# CPU.net
KiCad netlist of a schematic drawn in Altium Designer
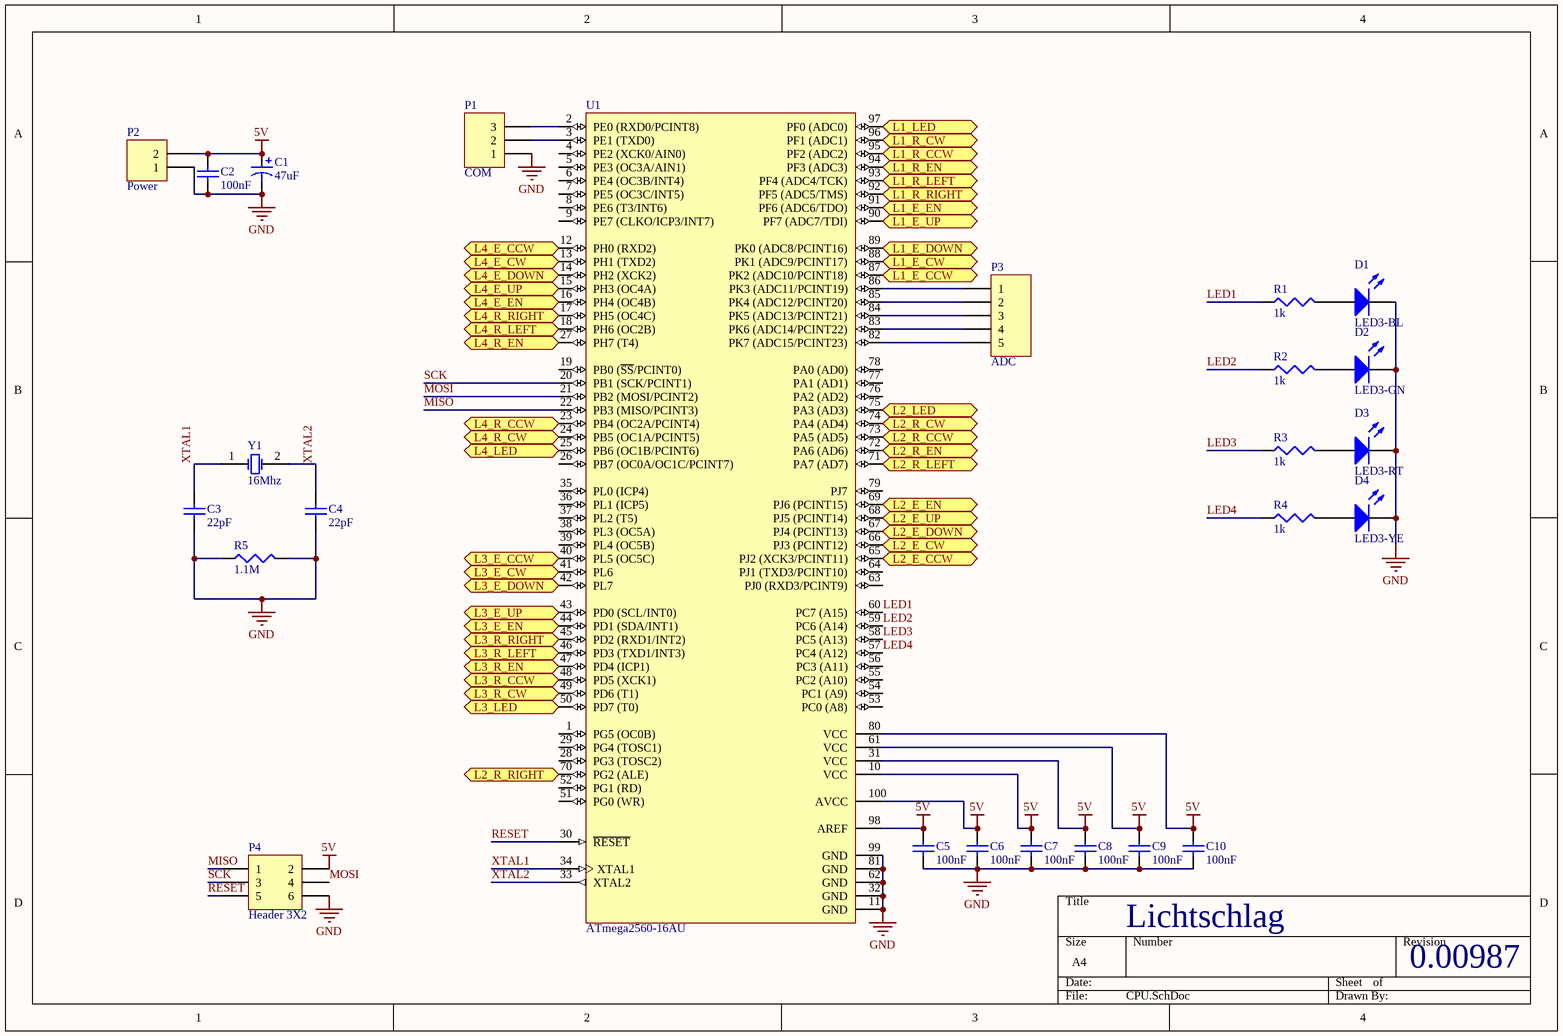
[diagram p0: CPU.SchDoc]

(export (version "E")
  (design (tool "Eeschema 10.0.6"))
  (components
    (comp (ref "C1")
      (value "47uF")
      (footprint "2220")
      (description "Polarized Capacitor (Surface Mount)")
      (fields (field (name "PUBLISHER") "Altium Limited"))
      (libsource (lib "Miscellaneous Devices") (part "Cap Pol3"))
    )
    (comp (ref "C2")
      (value "100nF")
      (footprint "2220")
      (description "Capacitor (Semiconductor SIM Model)")
      (fields (field (name "PUBLISHER") "Altium Limited"))
      (libsource (lib "Miscellaneous Devices") (part "Cap Semi"))
    )
    (comp (ref "C3")
      (value "22pF")
      (footprint "Miscellaneous Devices:6-0805_N")
      (description "Capacitor (Semiconductor SIM Model)")
      (fields (field (name "PUBLISHER") "Altium Limited"))
      (libsource (lib "Miscellaneous Devices") (part "Cap Semi"))
    )
    (comp (ref "C4")
      (value "22pF")
      (footprint "6-0805_N")
      (description "Capacitor (Semiconductor SIM Model)")
      (fields (field (name "PUBLISHER") "Altium Limited"))
      (libsource (lib "Miscellaneous Devices") (part "Cap Semi"))
    )
    (comp (ref "C5")
      (value "100nF")
      (footprint "2220")
      (description "Capacitor (Semiconductor SIM Model)")
      (fields (field (name "PUBLISHER") "Altium Limited"))
      (libsource (lib "Miscellaneous Devices") (part "Cap Semi"))
    )
    (comp (ref "C6")
      (value "100nF")
      (footprint "2220")
      (description "Capacitor (Semiconductor SIM Model)")
      (fields (field (name "PUBLISHER") "Altium Limited"))
      (libsource (lib "Miscellaneous Devices") (part "Cap Semi"))
    )
    (comp (ref "C7")
      (value "100nF")
      (footprint "2220")
      (description "Capacitor (Semiconductor SIM Model)")
      (fields (field (name "PUBLISHER") "Altium Limited"))
      (libsource (lib "Miscellaneous Devices") (part "Cap Semi"))
    )
    (comp (ref "C8")
      (value "100nF")
      (footprint "2220")
      (description "Capacitor (Semiconductor SIM Model)")
      (fields (field (name "PUBLISHER") "Altium Limited"))
      (libsource (lib "Miscellaneous Devices") (part "Cap Semi"))
    )
    (comp (ref "C9")
      (value "100nF")
      (footprint "2220")
      (description "Capacitor (Semiconductor SIM Model)")
      (fields (field (name "PUBLISHER") "Altium Limited"))
      (libsource (lib "Miscellaneous Devices") (part "Cap Semi"))
    )
    (comp (ref "C10")
      (value "100nF")
      (footprint "2220")
      (description "Capacitor (Semiconductor SIM Model)")
      (fields (field (name "PUBLISHER") "Altium Limited"))
      (libsource (lib "Miscellaneous Devices") (part "Cap Semi"))
    )
    (comp (ref "D1")
      (value "LED3-BL")
      (footprint "6-0805_N")
      (description "Typical BLUE SiC LED")
      (fields (field (name "PUBLISHER") "Altium Limited"))
      (libsource (lib "Miscellaneous Devices") (part "LED3"))
    )
    (comp (ref "D2")
      (value "LED3-GN")
      (footprint "6-0805_N")
      (description "Typical BLUE SiC LED")
      (fields (field (name "PUBLISHER") "Altium Limited"))
      (libsource (lib "Miscellaneous Devices") (part "LED3"))
    )
    (comp (ref "D3")
      (value "LED3-RT")
      (footprint "6-0805_N")
      (description "Typical BLUE SiC LED")
      (fields (field (name "PUBLISHER") "Altium Limited"))
      (libsource (lib "Miscellaneous Devices") (part "LED3"))
    )
    (comp (ref "D4")
      (value "LED3-YE")
      (footprint "6-0805_N")
      (description "Typical BLUE SiC LED")
      (fields (field (name "PUBLISHER") "Altium Limited"))
      (libsource (lib "Miscellaneous Devices") (part "LED3"))
    )
    (comp (ref "P1")
      (value "COM")
      (footprint "HDR1X3")
      (description "Header, 3-Pin")
      (fields (field (name "PUBLISHER") "Altium Limited"))
      (libsource (lib "Miscellaneous Connectors") (part "Header 3"))
    )
    (comp (ref "P2")
      (value "Power")
      (footprint "HDR1X2")
      (description "Header, 2-Pin")
      (fields (field (name "PUBLISHER") "Altium Limited"))
      (libsource (lib "Miscellaneous Connectors") (part "Header 2"))
    )
    (comp (ref "P3")
      (value "ADC")
      (footprint "HDR1X5")
      (description "Header, 5-Pin")
      (fields (field (name "PUBLISHER") "Altium Limited"))
      (libsource (lib "Miscellaneous Connectors") (part "Header 5"))
    )
    (comp (ref "P4")
      (value "Header 3X2")
      (footprint "HDR2X3")
      (description "Header, 3-Pin, Dual row")
      (fields (field (name "PUBLISHER") "Altium Limited"))
      (libsource (lib "Miscellaneous Connectors") (part "Header 3X2"))
    )
    (comp (ref "R1")
      (value "1k")
      (footprint "6-0805_N")
      (description "Resistor")
      (fields (field (name "PUBLISHER") "Altium Limited"))
      (libsource (lib "Miscellaneous Devices") (part "Res3"))
    )
    (comp (ref "R2")
      (value "1k")
      (footprint "6-0805_N")
      (description "Resistor")
      (fields (field (name "PUBLISHER") "Altium Limited"))
      (libsource (lib "Miscellaneous Devices") (part "Res3"))
    )
    (comp (ref "R3")
      (value "1k")
      (footprint "6-0805_N")
      (description "Resistor")
      (fields (field (name "PUBLISHER") "Altium Limited"))
      (libsource (lib "Miscellaneous Devices") (part "Res3"))
    )
    (comp (ref "R4")
      (value "1k")
      (footprint "6-0805_N")
      (description "Resistor")
      (fields (field (name "PUBLISHER") "Altium Limited"))
      (libsource (lib "Miscellaneous Devices") (part "Res3"))
    )
    (comp (ref "R5")
      (value "1.1M")
      (footprint "6-0805_N")
      (description "Resistor")
      (fields (field (name "PUBLISHER") "Altium Limited"))
      (libsource (lib "Miscellaneous Devices") (part "Res3"))
    )
    (comp (ref "U1")
      (value "ATmega2560-16AU")
      (footprint "100A_M")
      (libsource (lib "Altium Content Vault") (part "CMP-0095-00210-2"))
    )
    (comp (ref "Y1")
      (value "16Mhz")
      (footprint "R38")
      (description "Crystal Oscillator")
      (fields (field (name "PUBLISHER") "Altium Limited"))
      (libsource (lib "Miscellaneous Devices") (part "XTAL"))
    )
  )
  (nets
    (net (code "1") (name "/L1_E_CCW") (class "Default")
      (node (ref "U1") (pin "87") (pinfunction "PK2_(ADC10/PCINT18)_87") (pintype "bidirectional"))
    )
    (net (code "2") (name "/L1_E_CW") (class "Default")
      (node (ref "U1") (pin "88") (pinfunction "PK1_(ADC9/PCINT17)_88") (pintype "bidirectional"))
    )
    (net (code "3") (name "/L1_E_DOWN") (class "Default")
      (node (ref "U1") (pin "89") (pinfunction "PK0_(ADC8/PCINT16)_89") (pintype "bidirectional"))
    )
    (net (code "4") (name "/L1_E_EN") (class "Default")
      (node (ref "U1") (pin "91") (pinfunction "PF6_(ADC6/TDO)_91") (pintype "bidirectional"))
    )
    (net (code "5") (name "/L1_E_UP") (class "Default")
      (node (ref "U1") (pin "90") (pinfunction "PF7_(ADC7/TDI)_90") (pintype "bidirectional"))
    )
    (net (code "6") (name "/L1_LED") (class "Default")
      (node (ref "U1") (pin "97") (pinfunction "PF0_(ADC0)_97") (pintype "bidirectional"))
    )
    (net (code "7") (name "/L1_R_CCW") (class "Default")
      (node (ref "U1") (pin "95") (pinfunction "PF2_(ADC2)_95") (pintype "bidirectional"))
    )
    (net (code "8") (name "/L1_R_CW") (class "Default")
      (node (ref "U1") (pin "96") (pinfunction "PF1_(ADC1)_96") (pintype "bidirectional"))
    )
    (net (code "9") (name "/L1_R_EN") (class "Default")
      (node (ref "U1") (pin "94") (pinfunction "PF3_(ADC3)_94") (pintype "bidirectional"))
    )
    (net (code "10") (name "/L1_R_LEFT") (class "Default")
      (node (ref "U1") (pin "93") (pinfunction "PF4_(ADC4/TCK)_93") (pintype "bidirectional"))
    )
    (net (code "11") (name "/L1_R_RIGHT") (class "Default")
      (node (ref "U1") (pin "92") (pinfunction "PF5_(ADC5/TMS)_92") (pintype "bidirectional"))
    )
    (net (code "12") (name "/L2_E_CCW") (class "Default")
      (node (ref "U1") (pin "65") (pinfunction "PJ2_(XCK3/PCINT11)_65") (pintype "bidirectional"))
    )
    (net (code "13") (name "/L2_E_CW") (class "Default")
      (node (ref "U1") (pin "66") (pinfunction "PJ3_(PCINT12)_66") (pintype "bidirectional"))
    )
    (net (code "14") (name "/L2_E_DOWN") (class "Default")
      (node (ref "U1") (pin "67") (pinfunction "PJ4_(PCINT13)_67") (pintype "bidirectional"))
    )
    (net (code "15") (name "/L2_E_EN") (class "Default")
      (node (ref "U1") (pin "69") (pinfunction "PJ6_(PCINT15)_69") (pintype "bidirectional"))
    )
    (net (code "16") (name "/L2_E_UP") (class "Default")
      (node (ref "U1") (pin "68") (pinfunction "PJ5_(PCINT14)_68") (pintype "bidirectional"))
    )
    (net (code "17") (name "/L2_LED") (class "Default")
      (node (ref "U1") (pin "75") (pinfunction "PA3_(AD3)_75") (pintype "bidirectional"))
    )
    (net (code "18") (name "/L2_R_CCW") (class "Default")
      (node (ref "U1") (pin "73") (pinfunction "PA5_(AD5)_73") (pintype "bidirectional"))
    )
    (net (code "19") (name "/L2_R_CW") (class "Default")
      (node (ref "U1") (pin "74") (pinfunction "PA4_(AD4)_74") (pintype "bidirectional"))
    )
    (net (code "20") (name "/L2_R_EN") (class "Default")
      (node (ref "U1") (pin "72") (pinfunction "PA6_(AD6)_72") (pintype "bidirectional"))
    )
    (net (code "21") (name "/L2_R_LEFT") (class "Default")
      (node (ref "U1") (pin "71") (pinfunction "PA7_(AD7)_71") (pintype "bidirectional"))
    )
    (net (code "22") (name "/L2_R_RIGHT") (class "Default")
      (node (ref "U1") (pin "70") (pinfunction "PG2_(ALE)_70") (pintype "bidirectional"))
    )
    (net (code "23") (name "/L3_E_CCW") (class "Default")
      (node (ref "U1") (pin "40") (pinfunction "PL5_(OC5C)_40") (pintype "bidirectional"))
    )
    (net (code "24") (name "/L3_E_CW") (class "Default")
      (node (ref "U1") (pin "41") (pinfunction "PL6_41") (pintype "bidirectional"))
    )
    (net (code "25") (name "/L3_E_DOWN") (class "Default")
      (node (ref "U1") (pin "42") (pinfunction "PL7_42") (pintype "bidirectional"))
    )
    (net (code "26") (name "/L3_E_EN") (class "Default")
      (node (ref "U1") (pin "44") (pinfunction "PD1_(SDA/INT1)_44") (pintype "bidirectional"))
    )
    (net (code "27") (name "/L3_E_UP") (class "Default")
      (node (ref "U1") (pin "43") (pinfunction "PD0_(SCL/INT0)_43") (pintype "bidirectional"))
    )
    (net (code "28") (name "/L3_LED") (class "Default")
      (node (ref "U1") (pin "50") (pinfunction "PD7_(T0)_50") (pintype "bidirectional"))
    )
    (net (code "29") (name "/L3_R_CCW") (class "Default")
      (node (ref "U1") (pin "48") (pinfunction "PD5_(XCK1)_48") (pintype "bidirectional"))
    )
    (net (code "30") (name "/L3_R_CW") (class "Default")
      (node (ref "U1") (pin "49") (pinfunction "PD6_(T1)_49") (pintype "bidirectional"))
    )
    (net (code "31") (name "/L3_R_EN") (class "Default")
      (node (ref "U1") (pin "47") (pinfunction "PD4_(ICP1)_47") (pintype "bidirectional"))
    )
    (net (code "32") (name "/L3_R_LEFT") (class "Default")
      (node (ref "U1") (pin "46") (pinfunction "PD3_(TXD1/INT3)_46") (pintype "bidirectional"))
    )
    (net (code "33") (name "/L3_R_RIGHT") (class "Default")
      (node (ref "U1") (pin "45") (pinfunction "PD2_(RXD1/INT2)_45") (pintype "bidirectional"))
    )
    (net (code "34") (name "/L4_E_CCW") (class "Default")
      (node (ref "U1") (pin "12") (pinfunction "PH0_(RXD2)_12") (pintype "bidirectional"))
    )
    (net (code "35") (name "/L4_E_CW") (class "Default")
      (node (ref "U1") (pin "13") (pinfunction "PH1_(TXD2)_13") (pintype "bidirectional"))
    )
    (net (code "36") (name "/L4_E_DOWN") (class "Default")
      (node (ref "U1") (pin "14") (pinfunction "PH2_(XCK2)_14") (pintype "bidirectional"))
    )
    (net (code "37") (name "/L4_E_EN") (class "Default")
      (node (ref "U1") (pin "16") (pinfunction "PH4_(OC4B)_16") (pintype "bidirectional"))
    )
    (net (code "38") (name "/L4_E_UP") (class "Default")
      (node (ref "U1") (pin "15") (pinfunction "PH3_(OC4A)_15") (pintype "bidirectional"))
    )
    (net (code "39") (name "/L4_LED") (class "Default")
      (node (ref "U1") (pin "25") (pinfunction "PB6_(OC1B/PCINT6)_25") (pintype "bidirectional"))
    )
    (net (code "40") (name "/L4_R_CCW") (class "Default")
      (node (ref "U1") (pin "23") (pinfunction "PB4_(OC2A/PCINT4)_23") (pintype "bidirectional"))
    )
    (net (code "41") (name "/L4_R_CW") (class "Default")
      (node (ref "U1") (pin "24") (pinfunction "PB5_(OC1A/PCINT5)_24") (pintype "bidirectional"))
    )
    (net (code "42") (name "/L4_R_EN") (class "Default")
      (node (ref "U1") (pin "27") (pinfunction "PH7_(T4)_27") (pintype "bidirectional"))
    )
    (net (code "43") (name "/L4_R_LEFT") (class "Default")
      (node (ref "U1") (pin "18") (pinfunction "PH6_(OC2B)_18") (pintype "bidirectional"))
    )
    (net (code "44") (name "/L4_R_RIGHT") (class "Default")
      (node (ref "U1") (pin "17") (pinfunction "PH5_(OC4C)_17") (pintype "bidirectional"))
    )
    (net (code "45") (name "/LED1") (class "Default")
      (node (ref "R1") (pin "1") (pinfunction "1_1") (pintype "passive"))
      (node (ref "U1") (pin "60") (pinfunction "PC7_(A15)_60") (pintype "bidirectional"))
    )
    (net (code "46") (name "/LED2") (class "Default")
      (node (ref "R2") (pin "1") (pinfunction "1_1") (pintype "passive"))
      (node (ref "U1") (pin "59") (pinfunction "PC6_(A14)_59") (pintype "bidirectional"))
    )
    (net (code "47") (name "/LED3") (class "Default")
      (node (ref "R3") (pin "1") (pinfunction "1_1") (pintype "passive"))
      (node (ref "U1") (pin "58") (pinfunction "PC5_(A13)_58") (pintype "bidirectional"))
    )
    (net (code "48") (name "/LED4") (class "Default")
      (node (ref "R4") (pin "1") (pinfunction "1_1") (pintype "passive"))
      (node (ref "U1") (pin "57") (pinfunction "PC4_(A12)_57") (pintype "bidirectional"))
    )
    (net (code "49") (name "/MISO") (class "Default")
      (node (ref "P4") (pin "1") (pinfunction "1_1") (pintype "passive"))
      (node (ref "U1") (pin "22") (pinfunction "PB3_(MISO/PCINT3)_22") (pintype "bidirectional"))
    )
    (net (code "50") (name "/MOSI") (class "Default")
      (node (ref "P4") (pin "4") (pinfunction "4_4") (pintype "passive"))
      (node (ref "U1") (pin "21") (pinfunction "PB2_(MOSI/PCINT2)_21") (pintype "bidirectional"))
    )
    (net (code "51") (name "/RESET") (class "Default")
      (node (ref "P4") (pin "5") (pinfunction "5_5") (pintype "passive"))
      (node (ref "U1") (pin "30") (pinfunction "~{RESET}_30") (pintype "input"))
    )
    (net (code "52") (name "/SCK") (class "Default")
      (node (ref "P4") (pin "3") (pinfunction "3_3") (pintype "passive"))
      (node (ref "U1") (pin "20") (pinfunction "PB1_(SCK/PCINT1)_20") (pintype "bidirectional"))
    )
    (net (code "53") (name "/XTAL1") (class "Default")
      (node (ref "C3") (pin "2") (pinfunction "2_2") (pintype "passive"))
      (node (ref "U1") (pin "34") (pinfunction "XTAL1_34") (pintype "input"))
      (node (ref "Y1") (pin "1") (pinfunction "OSC1_1") (pintype "passive"))
    )
    (net (code "54") (name "/XTAL2") (class "Default")
      (node (ref "C4") (pin "2") (pinfunction "2_2") (pintype "passive"))
      (node (ref "U1") (pin "33") (pinfunction "XTAL2_33") (pintype "output"))
      (node (ref "Y1") (pin "2") (pinfunction "OSC2_2") (pintype "passive"))
    )
    (net (code "55") (name "5V") (class "Default")
      (node (ref "C1") (pin "1") (pinfunction "1_1") (pintype "passive"))
      (node (ref "C10") (pin "2") (pinfunction "2_2") (pintype "passive"))
      (node (ref "C2") (pin "2") (pinfunction "2_2") (pintype "passive"))
      (node (ref "C5") (pin "2") (pinfunction "2_2") (pintype "passive"))
      (node (ref "C6") (pin "2") (pinfunction "2_2") (pintype "passive"))
      (node (ref "C7") (pin "2") (pinfunction "2_2") (pintype "passive"))
      (node (ref "C8") (pin "2") (pinfunction "2_2") (pintype "passive"))
      (node (ref "C9") (pin "2") (pinfunction "2_2") (pintype "passive"))
      (node (ref "P2") (pin "2") (pinfunction "2_2") (pintype "passive"))
      (node (ref "P4") (pin "2") (pinfunction "2_2") (pintype "passive"))
      (node (ref "U1") (pin "10") (pinfunction "VCC_10") (pintype "power_in"))
      (node (ref "U1") (pin "100") (pinfunction "AVCC_100") (pintype "power_in"))
      (node (ref "U1") (pin "31") (pinfunction "VCC_31") (pintype "power_in"))
      (node (ref "U1") (pin "61") (pinfunction "VCC_61") (pintype "power_in"))
      (node (ref "U1") (pin "80") (pinfunction "VCC_80") (pintype "power_in"))
      (node (ref "U1") (pin "98") (pinfunction "AREF_98") (pintype "power_in"))
    )
    (net (code "56") (name "GND") (class "Default")
      (node (ref "C1") (pin "2") (pinfunction "2_2") (pintype "passive"))
      (node (ref "C10") (pin "1") (pinfunction "1_1") (pintype "passive"))
      (node (ref "C2") (pin "1") (pinfunction "1_1") (pintype "passive"))
      (node (ref "C3") (pin "1") (pinfunction "1_1") (pintype "passive"))
      (node (ref "C4") (pin "1") (pinfunction "1_1") (pintype "passive"))
      (node (ref "C5") (pin "1") (pinfunction "1_1") (pintype "passive"))
      (node (ref "C6") (pin "1") (pinfunction "1_1") (pintype "passive"))
      (node (ref "C7") (pin "1") (pinfunction "1_1") (pintype "passive"))
      (node (ref "C8") (pin "1") (pinfunction "1_1") (pintype "passive"))
      (node (ref "C9") (pin "1") (pinfunction "1_1") (pintype "passive"))
      (node (ref "D1") (pin "2") (pinfunction "K_2") (pintype "passive"))
      (node (ref "D2") (pin "2") (pinfunction "K_2") (pintype "passive"))
      (node (ref "D3") (pin "2") (pinfunction "K_2") (pintype "passive"))
      (node (ref "D4") (pin "2") (pinfunction "K_2") (pintype "passive"))
      (node (ref "P1") (pin "1") (pinfunction "1_1") (pintype "passive"))
      (node (ref "P2") (pin "1") (pinfunction "1_1") (pintype "passive"))
      (node (ref "P4") (pin "6") (pinfunction "6_6") (pintype "passive"))
      (node (ref "R5") (pin "1") (pinfunction "1_1") (pintype "passive"))
      (node (ref "R5") (pin "2") (pinfunction "2_2") (pintype "passive"))
      (node (ref "U1") (pin "11") (pinfunction "GND_11") (pintype "power_in"))
      (node (ref "U1") (pin "32") (pinfunction "GND_32") (pintype "power_in"))
      (node (ref "U1") (pin "62") (pinfunction "GND_62") (pintype "power_in"))
      (node (ref "U1") (pin "81") (pinfunction "GND_81") (pintype "power_in"))
      (node (ref "U1") (pin "99") (pinfunction "GND_99") (pintype "power_in"))
    )
    (net (code "57") (name "Net-(D1-A)") (class "Default")
      (node (ref "D1") (pin "1") (pinfunction "A_1") (pintype "passive"))
      (node (ref "R1") (pin "2") (pinfunction "2_2") (pintype "passive"))
    )
    (net (code "58") (name "Net-(D2-A)") (class "Default")
      (node (ref "D2") (pin "1") (pinfunction "A_1") (pintype "passive"))
      (node (ref "R2") (pin "2") (pinfunction "2_2") (pintype "passive"))
    )
    (net (code "59") (name "Net-(D3-A)") (class "Default")
      (node (ref "D3") (pin "1") (pinfunction "A_1") (pintype "passive"))
      (node (ref "R3") (pin "2") (pinfunction "2_2") (pintype "passive"))
    )
    (net (code "60") (name "Net-(D4-A)") (class "Default")
      (node (ref "D4") (pin "1") (pinfunction "A_1") (pintype "passive"))
      (node (ref "R4") (pin "2") (pinfunction "2_2") (pintype "passive"))
    )
    (net (code "61") (name "Net-(U1-PE0_(RXD0{slash}PCINT8))") (class "Default")
      (node (ref "P1") (pin "3") (pinfunction "3_3") (pintype "passive"))
      (node (ref "U1") (pin "2") (pinfunction "PE0_(RXD0/PCINT8)_2") (pintype "bidirectional"))
    )
    (net (code "62") (name "Net-(U1-PE1_(TXD0))") (class "Default")
      (node (ref "P1") (pin "2") (pinfunction "2_2") (pintype "passive"))
      (node (ref "U1") (pin "3") (pinfunction "PE1_(TXD0)_3") (pintype "bidirectional"))
    )
    (net (code "63") (name "Net-(U1-PK3_(ADC11{slash}PCINT19))") (class "Default")
      (node (ref "P3") (pin "1") (pinfunction "1_1") (pintype "passive"))
      (node (ref "U1") (pin "86") (pinfunction "PK3_(ADC11/PCINT19)_86") (pintype "bidirectional"))
    )
    (net (code "64") (name "Net-(U1-PK4_(ADC12{slash}PCINT20))") (class "Default")
      (node (ref "P3") (pin "2") (pinfunction "2_2") (pintype "passive"))
      (node (ref "U1") (pin "85") (pinfunction "PK4_(ADC12/PCINT20)_85") (pintype "bidirectional"))
    )
    (net (code "65") (name "Net-(U1-PK5_(ADC13{slash}PCINT21))") (class "Default")
      (node (ref "P3") (pin "3") (pinfunction "3_3") (pintype "passive"))
      (node (ref "U1") (pin "84") (pinfunction "PK5_(ADC13/PCINT21)_84") (pintype "bidirectional"))
    )
    (net (code "66") (name "Net-(U1-PK6_(ADC14{slash}PCINT22))") (class "Default")
      (node (ref "P3") (pin "4") (pinfunction "4_4") (pintype "passive"))
      (node (ref "U1") (pin "83") (pinfunction "PK6_(ADC14/PCINT22)_83") (pintype "bidirectional"))
    )
    (net (code "67") (name "Net-(U1-PK7_(ADC15{slash}PCINT23))") (class "Default")
      (node (ref "P3") (pin "5") (pinfunction "5_5") (pintype "passive"))
      (node (ref "U1") (pin "82") (pinfunction "PK7_(ADC15/PCINT23)_82") (pintype "bidirectional"))
    )
    (net (code "68") (name "unconnected-(U1-PA0_(AD0)-Pad78)") (class "Default")
      (node (ref "U1") (pin "78") (pinfunction "PA0_(AD0)_78") (pintype "bidirectional"))
    )
    (net (code "69") (name "unconnected-(U1-PA1_(AD1)-Pad77)") (class "Default")
      (node (ref "U1") (pin "77") (pinfunction "PA1_(AD1)_77") (pintype "bidirectional"))
    )
    (net (code "70") (name "unconnected-(U1-PA2_(AD2)-Pad76)") (class "Default")
      (node (ref "U1") (pin "76") (pinfunction "PA2_(AD2)_76") (pintype "bidirectional"))
    )
    (net (code "71") (name "unconnected-(U1-PB0_(~{SS}{slash}PCINT0)-Pad19)") (class "Default")
      (node (ref "U1") (pin "19") (pinfunction "PB0_(~{SS}/PCINT0)_19") (pintype "bidirectional"))
    )
    (net (code "72") (name "unconnected-(U1-PB7_(OC0A{slash}OC1C{slash}PCINT7)-Pad26)") (class "Default")
      (node (ref "U1") (pin "26") (pinfunction "PB7_(OC0A/OC1C/PCINT7)_26") (pintype "bidirectional"))
    )
    (net (code "73") (name "unconnected-(U1-PC0_(A8)-Pad53)") (class "Default")
      (node (ref "U1") (pin "53") (pinfunction "PC0_(A8)_53") (pintype "bidirectional"))
    )
    (net (code "74") (name "unconnected-(U1-PC1_(A9)-Pad54)") (class "Default")
      (node (ref "U1") (pin "54") (pinfunction "PC1_(A9)_54") (pintype "bidirectional"))
    )
    (net (code "75") (name "unconnected-(U1-PC2_(A10)-Pad55)") (class "Default")
      (node (ref "U1") (pin "55") (pinfunction "PC2_(A10)_55") (pintype "bidirectional"))
    )
    (net (code "76") (name "unconnected-(U1-PC3_(A11)-Pad56)") (class "Default")
      (node (ref "U1") (pin "56") (pinfunction "PC3_(A11)_56") (pintype "bidirectional"))
    )
    (net (code "77") (name "unconnected-(U1-PE2_(XCK0{slash}AIN0)-Pad4)") (class "Default")
      (node (ref "U1") (pin "4") (pinfunction "PE2_(XCK0/AIN0)_4") (pintype "bidirectional"))
    )
    (net (code "78") (name "unconnected-(U1-PE3_(OC3A{slash}AIN1)-Pad5)") (class "Default")
      (node (ref "U1") (pin "5") (pinfunction "PE3_(OC3A/AIN1)_5") (pintype "bidirectional"))
    )
    (net (code "79") (name "unconnected-(U1-PE4_(OC3B{slash}INT4)-Pad6)") (class "Default")
      (node (ref "U1") (pin "6") (pinfunction "PE4_(OC3B/INT4)_6") (pintype "bidirectional"))
    )
    (net (code "80") (name "unconnected-(U1-PE5_(OC3C{slash}INT5)-Pad7)") (class "Default")
      (node (ref "U1") (pin "7") (pinfunction "PE5_(OC3C/INT5)_7") (pintype "bidirectional"))
    )
    (net (code "81") (name "unconnected-(U1-PE6_(T3{slash}INT6)-Pad8)") (class "Default")
      (node (ref "U1") (pin "8") (pinfunction "PE6_(T3/INT6)_8") (pintype "bidirectional"))
    )
    (net (code "82") (name "unconnected-(U1-PE7_(CLKO{slash}ICP3{slash}INT7)-Pad9)") (class "Default")
      (node (ref "U1") (pin "9") (pinfunction "PE7_(CLKO/ICP3/INT7)_9") (pintype "bidirectional"))
    )
    (net (code "83") (name "unconnected-(U1-PG0_(WR)-Pad51)") (class "Default")
      (node (ref "U1") (pin "51") (pinfunction "PG0_(WR)_51") (pintype "bidirectional"))
    )
    (net (code "84") (name "unconnected-(U1-PG1_(RD)-Pad52)") (class "Default")
      (node (ref "U1") (pin "52") (pinfunction "PG1_(RD)_52") (pintype "bidirectional"))
    )
    (net (code "85") (name "unconnected-(U1-PG3_(TOSC2)-Pad28)") (class "Default")
      (node (ref "U1") (pin "28") (pinfunction "PG3_(TOSC2)_28") (pintype "bidirectional"))
    )
    (net (code "86") (name "unconnected-(U1-PG4_(TOSC1)-Pad29)") (class "Default")
      (node (ref "U1") (pin "29") (pinfunction "PG4_(TOSC1)_29") (pintype "bidirectional"))
    )
    (net (code "87") (name "unconnected-(U1-PG5_(OC0B)-Pad1)") (class "Default")
      (node (ref "U1") (pin "1") (pinfunction "PG5_(OC0B)_1") (pintype "bidirectional"))
    )
    (net (code "88") (name "unconnected-(U1-PJ0_(RXD3{slash}PCINT9)-Pad63)") (class "Default")
      (node (ref "U1") (pin "63") (pinfunction "PJ0_(RXD3/PCINT9)_63") (pintype "bidirectional"))
    )
    (net (code "89") (name "unconnected-(U1-PJ1_(TXD3{slash}PCINT10)-Pad64)") (class "Default")
      (node (ref "U1") (pin "64") (pinfunction "PJ1_(TXD3/PCINT10)_64") (pintype "bidirectional"))
    )
    (net (code "90") (name "unconnected-(U1-PJ7-Pad79)") (class "Default")
      (node (ref "U1") (pin "79") (pinfunction "PJ7_79") (pintype "bidirectional"))
    )
    (net (code "91") (name "unconnected-(U1-PL0_(ICP4)-Pad35)") (class "Default")
      (node (ref "U1") (pin "35") (pinfunction "PL0_(ICP4)_35") (pintype "bidirectional"))
    )
    (net (code "92") (name "unconnected-(U1-PL1_(ICP5)-Pad36)") (class "Default")
      (node (ref "U1") (pin "36") (pinfunction "PL1_(ICP5)_36") (pintype "bidirectional"))
    )
    (net (code "93") (name "unconnected-(U1-PL2_(T5)-Pad37)") (class "Default")
      (node (ref "U1") (pin "37") (pinfunction "PL2_(T5)_37") (pintype "bidirectional"))
    )
    (net (code "94") (name "unconnected-(U1-PL3_(OC5A)-Pad38)") (class "Default")
      (node (ref "U1") (pin "38") (pinfunction "PL3_(OC5A)_38") (pintype "bidirectional"))
    )
    (net (code "95") (name "unconnected-(U1-PL4_(OC5B)-Pad39)") (class "Default")
      (node (ref "U1") (pin "39") (pinfunction "PL4_(OC5B)_39") (pintype "bidirectional"))
    )
  )
)
